# gps.net
KiCad netlist of a schematic drawn in Altium Designer
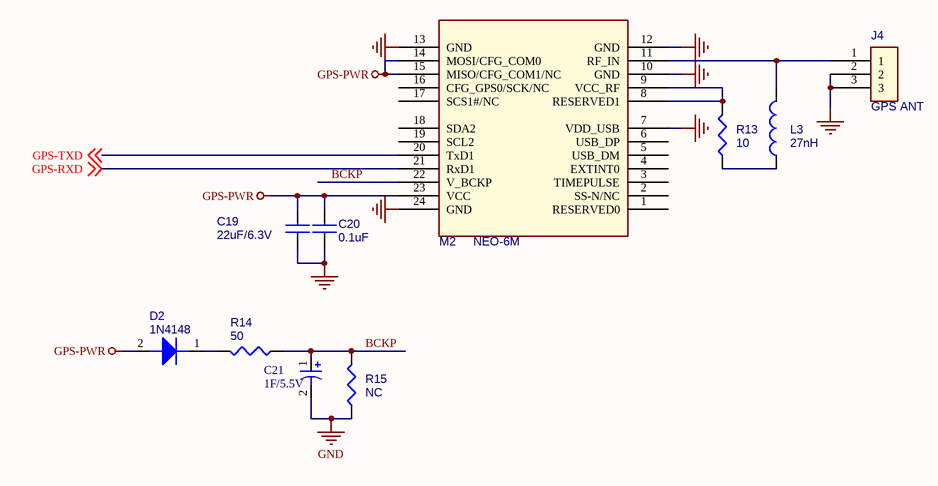
[diagram p0: gps.SchDoc]

(export (version "E")
  (design (tool "Eeschema 10.0.6"))
  (components
    (comp (ref "C19") (value "22uF/6.3V") (libsource (lib "*") (part "P_CAP NP")))
    (comp (ref "C20") (value "0.1uF") (libsource (lib "*") (part "P_CAP NP")))
    (comp (ref "C21")
      (value "1F/5.5V")
      (footprint "SCAP")
      (description "Polarized Capacitor (Radial)")
      (libsource (lib "Miscellaneous Devices") (part "Cap Pol1"))
    )
    (comp (ref "D2")
      (value "1N4148")
      (footprint "MINI-MELF")
      (libsource (lib "*") (part "1N4148WS-7-F_SOD323-2"))
    )
    (comp (ref "J4") (value "GPS ANT") (footprint "ANT") (libsource (lib "*") (part "HRS_U_0.FL-R-SMT-10")))
    (comp (ref "L3")
      (value "27nH")
      (footprint "0603")
      (libsource (lib "*") (part "2.2UH_LPS3015-222MLC_1.5A_20%~D"))
    )
    (comp (ref "M2") (value "NEO-6M") (footprint "NEO-6") (libsource (lib "*") (part "NEO-5M")))
    (comp (ref "R13") (value "10") (footprint "0603") (libsource (lib "*") (part "P_R")))
    (comp (ref "R14") (value "50") (footprint "0603") (libsource (lib "*") (part "P_R")))
    (comp (ref "R15") (value "NC") (footprint "0603") (libsource (lib "*") (part "P_R")))
  )
  (nets
    (net (code "1") (name "/BCKP") (class "Default")
      (node (ref "C21") (pin "1") (pinfunction "1_1") (pintype "passive"))
      (node (ref "M2") (pin "22") (pinfunction "V_BCKP_22") (pintype "passive"))
      (node (ref "R14") (pin "1") (pinfunction "1_1") (pintype "passive"))
      (node (ref "R15") (pin "2") (pinfunction "2_2") (pintype "passive"))
    )
    (net (code "2") (name "GND") (class "Default")
      (node (ref "C19") (pin "2") (pinfunction "2_2") (pintype "passive"))
      (node (ref "C20") (pin "2") (pinfunction "2_2") (pintype "passive"))
      (node (ref "C21") (pin "2") (pinfunction "2_2") (pintype "passive"))
      (node (ref "J4") (pin "2") (pinfunction "2_2") (pintype "passive"))
      (node (ref "J4") (pin "3") (pinfunction "3_3") (pintype "passive"))
      (node (ref "M2") (pin "10") (pinfunction "GND_10") (pintype "power_in"))
      (node (ref "M2") (pin "12") (pinfunction "GND_12") (pintype "power_in"))
      (node (ref "M2") (pin "13") (pinfunction "GND_13") (pintype "power_in"))
      (node (ref "M2") (pin "24") (pinfunction "GND_24") (pintype "power_in"))
      (node (ref "M2") (pin "7") (pinfunction "VDD_USB_7") (pintype "passive"))
      (node (ref "R15") (pin "1") (pinfunction "1_1") (pintype "passive"))
    )
    (net (code "3") (name "GPS-PWR") (class "Default")
      (node (ref "C19") (pin "1") (pinfunction "1_1") (pintype "passive"))
      (node (ref "C20") (pin "1") (pinfunction "1_1") (pintype "passive"))
      (node (ref "D2") (pin "2") (pinfunction "2_2") (pintype "passive"))
      (node (ref "M2") (pin "14") (pinfunction "MOSI/CFG_COM0_14") (pintype "passive"))
      (node (ref "M2") (pin "15") (pinfunction "MISO/CFG_COM1/NC_15") (pintype "passive"))
      (node (ref "M2") (pin "23") (pinfunction "VCC_23") (pintype "passive"))
    )
    (net (code "4") (name "GPS-RXD") (class "Default")
      (node (ref "M2") (pin "21") (pinfunction "RxD1_21") (pintype "passive"))
    )
    (net (code "5") (name "GPS-TXD") (class "Default")
      (node (ref "M2") (pin "20") (pinfunction "TxD1_20") (pintype "passive"))
    )
    (net (code "6") (name "Net-(D2-Pad1)") (class "Default")
      (node (ref "D2") (pin "1") (pinfunction "1_1") (pintype "passive"))
      (node (ref "R14") (pin "2") (pinfunction "2_2") (pintype "passive"))
    )
    (net (code "7") (name "Net-(L3-Pad1)") (class "Default")
      (node (ref "L3") (pin "1") (pinfunction "1_1") (pintype "passive"))
      (node (ref "R13") (pin "1") (pinfunction "1_1") (pintype "passive"))
    )
    (net (code "8") (name "Net-(M2-RESERVED1)") (class "Default")
      (node (ref "M2") (pin "8") (pinfunction "RESERVED1_8") (pintype "passive"))
      (node (ref "M2") (pin "9") (pinfunction "VCC_RF_9") (pintype "passive"))
      (node (ref "R13") (pin "2") (pinfunction "2_2") (pintype "passive"))
    )
    (net (code "9") (name "Net-(M2-RF_IN)") (class "Default")
      (node (ref "J4") (pin "1") (pinfunction "1_1") (pintype "passive"))
      (node (ref "L3") (pin "2") (pinfunction "2_2") (pintype "passive"))
      (node (ref "M2") (pin "11") (pinfunction "RF_IN_11") (pintype "passive"))
    )
    (net (code "10") (name "unconnected-(M2-CFG_GPS0{slash}SCK{slash}NC-Pad16)") (class "Default")
      (node (ref "M2") (pin "16") (pinfunction "CFG_GPS0/SCK/NC_16") (pintype "passive"))
    )
    (net (code "11") (name "unconnected-(M2-EXTINT0-Pad4)") (class "Default")
      (node (ref "M2") (pin "4") (pinfunction "EXTINT0_4") (pintype "passive"))
    )
    (net (code "12") (name "unconnected-(M2-RESERVED0-Pad1)") (class "Default")
      (node (ref "M2") (pin "1") (pinfunction "RESERVED0_1") (pintype "passive"))
    )
    (net (code "13") (name "unconnected-(M2-SCL2-Pad19)") (class "Default")
      (node (ref "M2") (pin "19") (pinfunction "SCL2_19") (pintype "passive"))
    )
    (net (code "14") (name "unconnected-(M2-SCS1#{slash}NC-Pad17)") (class "Default")
      (node (ref "M2") (pin "17") (pinfunction "SCS1#/NC_17") (pintype "passive"))
    )
    (net (code "15") (name "unconnected-(M2-SDA2-Pad18)") (class "Default")
      (node (ref "M2") (pin "18") (pinfunction "SDA2_18") (pintype "passive"))
    )
    (net (code "16") (name "unconnected-(M2-SS-N{slash}NC-Pad2)") (class "Default")
      (node (ref "M2") (pin "2") (pinfunction "SS-N/NC_2") (pintype "passive"))
    )
    (net (code "17") (name "unconnected-(M2-TIMEPULSE-Pad3)") (class "Default")
      (node (ref "M2") (pin "3") (pinfunction "TIMEPULSE_3") (pintype "passive"))
    )
    (net (code "18") (name "unconnected-(M2-USB_DM-Pad5)") (class "Default")
      (node (ref "M2") (pin "5") (pinfunction "USB_DM_5") (pintype "passive"))
    )
    (net (code "19") (name "unconnected-(M2-USB_DP-Pad6)") (class "Default")
      (node (ref "M2") (pin "6") (pinfunction "USB_DP_6") (pintype "passive"))
    )
  )
)
